# IotaWatt4_4.net
KiCad netlist of a schematic drawn in EAGLE
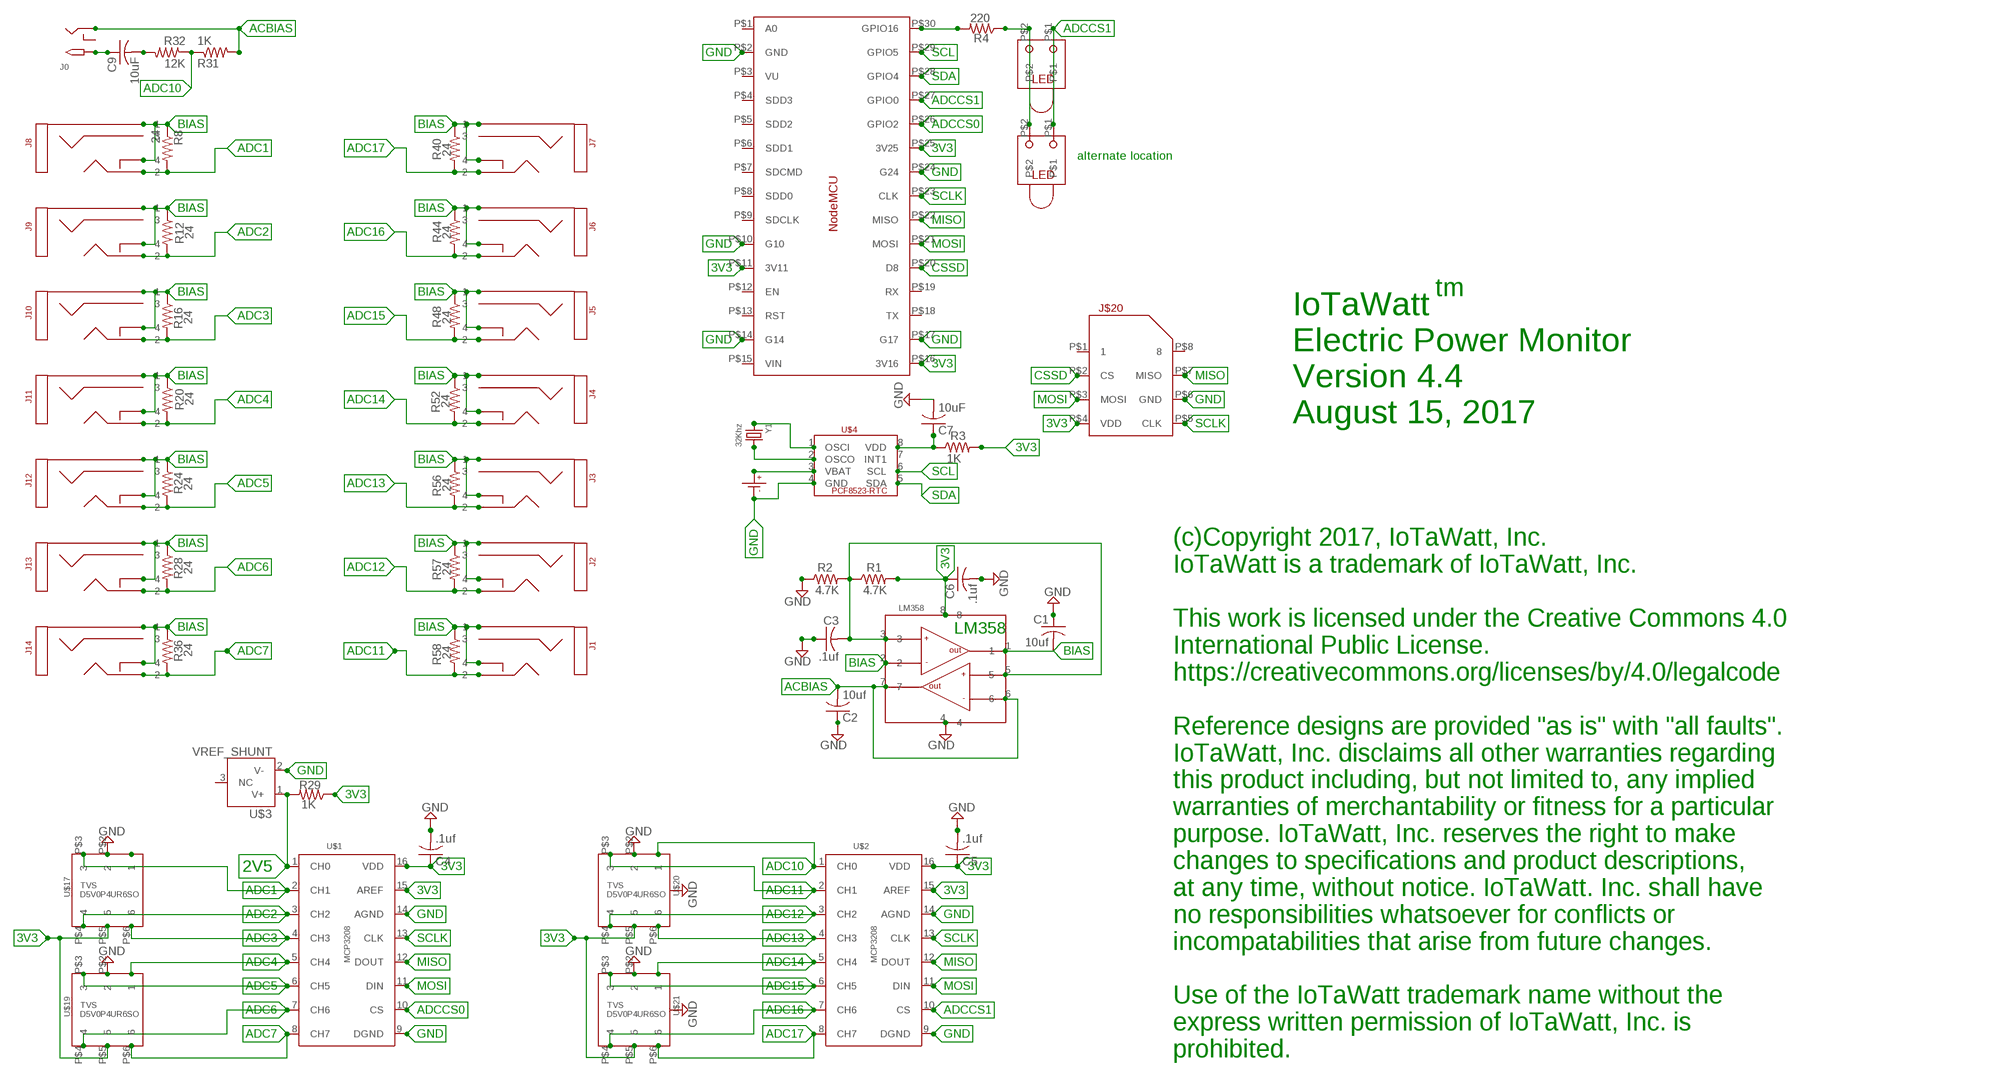
[diagram p0: schematic, sheet 1]

(export (version "E")
  (design (tool "Eeschema 10.0.6"))
  (components
    (comp (ref "C1")
      (value "10uf")
      (footprint "eagle-import:C0805")
      (libsource (lib "eagle-import") (part "C-USC0805"))
    )
    (comp (ref "C2")
      (value "10uf")
      (footprint "eagle-import:C0805")
      (libsource (lib "eagle-import") (part "C-USC0805"))
    )
    (comp (ref "C3")
      (value ".1uf")
      (footprint "eagle-import:C0805")
      (libsource (lib "eagle-import") (part "C-USC0805"))
    )
    (comp (ref "C4")
      (value ".1uf")
      (footprint "eagle-import:C0805")
      (libsource (lib "eagle-import") (part "C-USC0805"))
    )
    (comp (ref "C5")
      (value ".1uf")
      (footprint "eagle-import:C0805")
      (libsource (lib "eagle-import") (part "C-USC0805"))
    )
    (comp (ref "C6")
      (value ".1uf")
      (footprint "eagle-import:C0805")
      (libsource (lib "eagle-import") (part "C-USC0805"))
    )
    (comp (ref "C7")
      (value "10uF")
      (footprint "eagle-import:C0805")
      (libsource (lib "eagle-import") (part "C-USC0805"))
    )
    (comp (ref "C9")
      (value "10uF")
      (footprint "eagle-import:C0805")
      (libsource (lib "eagle-import") (part "C-USC0805"))
    )
    (comp (ref "J$20")
      (value "MICROSD_PUSH/PULL")
      (footprint "eagle-import:MICROSD")
      (libsource (lib "eagle-import") (part "MICROSD_PUSH/PULL"))
    )
    (comp (ref "J0")
      (value "2.1MMJACKSMT")
      (footprint "eagle-import:DCJACK_2MM_SMT")
      (libsource (lib "eagle-import") (part "2.1MMJACKSMT"))
    )
    (comp (ref "J1")
      (value "STEREO_SMD")
      (footprint "eagle-import:STEREO_SMT")
      (libsource (lib "eagle-import") (part "STEREO_SMD"))
    )
    (comp (ref "J2")
      (value "STEREO_SMD")
      (footprint "eagle-import:STEREO_SMT")
      (libsource (lib "eagle-import") (part "STEREO_SMD"))
    )
    (comp (ref "J3")
      (value "STEREO_SMD")
      (footprint "eagle-import:STEREO_SMT")
      (libsource (lib "eagle-import") (part "STEREO_SMD"))
    )
    (comp (ref "J4")
      (value "STEREO_SMD")
      (footprint "eagle-import:STEREO_SMT")
      (libsource (lib "eagle-import") (part "STEREO_SMD"))
    )
    (comp (ref "J5")
      (value "STEREO_SMD")
      (footprint "eagle-import:STEREO_SMT")
      (libsource (lib "eagle-import") (part "STEREO_SMD"))
    )
    (comp (ref "J6")
      (value "STEREO_SMD")
      (footprint "eagle-import:STEREO_SMT")
      (libsource (lib "eagle-import") (part "STEREO_SMD"))
    )
    (comp (ref "J7")
      (value "STEREO_SMD")
      (footprint "eagle-import:STEREO_SMT")
      (libsource (lib "eagle-import") (part "STEREO_SMD"))
    )
    (comp (ref "J8")
      (value "STEREO_SMD")
      (footprint "eagle-import:STEREO_SMT")
      (libsource (lib "eagle-import") (part "STEREO_SMD"))
    )
    (comp (ref "J9")
      (value "STEREO_SMD")
      (footprint "eagle-import:STEREO_SMT")
      (libsource (lib "eagle-import") (part "STEREO_SMD"))
    )
    (comp (ref "J10")
      (value "STEREO_SMD")
      (footprint "eagle-import:STEREO_SMT")
      (libsource (lib "eagle-import") (part "STEREO_SMD"))
    )
    (comp (ref "J11")
      (value "STEREO_SMD")
      (footprint "eagle-import:STEREO_SMT")
      (libsource (lib "eagle-import") (part "STEREO_SMD"))
    )
    (comp (ref "J12")
      (value "STEREO_SMD")
      (footprint "eagle-import:STEREO_SMT")
      (libsource (lib "eagle-import") (part "STEREO_SMD"))
    )
    (comp (ref "J13")
      (value "STEREO_SMD")
      (footprint "eagle-import:STEREO_SMT")
      (libsource (lib "eagle-import") (part "STEREO_SMD"))
    )
    (comp (ref "J14")
      (value "STEREO_SMD")
      (footprint "eagle-import:STEREO_SMT")
      (libsource (lib "eagle-import") (part "STEREO_SMD"))
    )
    (comp (ref "R1")
      (value "4.7K")
      (footprint "eagle-import:R0805")
      (libsource (lib "eagle-import") (part "R-US_R0805"))
    )
    (comp (ref "R2")
      (value "4.7K")
      (footprint "eagle-import:R0805")
      (libsource (lib "eagle-import") (part "R-US_R0805"))
    )
    (comp (ref "R3")
      (value "1K")
      (footprint "eagle-import:R0805")
      (libsource (lib "eagle-import") (part "R-US_R0805"))
    )
    (comp (ref "R4")
      (value "220")
      (footprint "eagle-import:R0805")
      (libsource (lib "eagle-import") (part "R-US_R0805"))
    )
    (comp (ref "R8")
      (value "24")
      (footprint "eagle-import:R0805")
      (libsource (lib "eagle-import") (part "R-US_R0805"))
    )
    (comp (ref "R12")
      (value "24")
      (footprint "eagle-import:R0805")
      (libsource (lib "eagle-import") (part "R-US_R0805"))
    )
    (comp (ref "R16")
      (value "24")
      (footprint "eagle-import:R0805")
      (libsource (lib "eagle-import") (part "R-US_R0805"))
    )
    (comp (ref "R20")
      (value "24")
      (footprint "eagle-import:R0805")
      (libsource (lib "eagle-import") (part "R-US_R0805"))
    )
    (comp (ref "R24")
      (value "24")
      (footprint "eagle-import:R0805")
      (libsource (lib "eagle-import") (part "R-US_R0805"))
    )
    (comp (ref "R28")
      (value "24")
      (footprint "eagle-import:R0805")
      (libsource (lib "eagle-import") (part "R-US_R0805"))
    )
    (comp (ref "R29")
      (value "1K")
      (footprint "eagle-import:R0805")
      (libsource (lib "eagle-import") (part "R-US_R0805"))
    )
    (comp (ref "R31")
      (value "1K")
      (footprint "eagle-import:R0805")
      (libsource (lib "eagle-import") (part "R-US_R0805"))
    )
    (comp (ref "R32")
      (value "12K")
      (footprint "eagle-import:R0805")
      (libsource (lib "eagle-import") (part "R-US_R0805"))
    )
    (comp (ref "R36")
      (value "24")
      (footprint "eagle-import:R0805")
      (libsource (lib "eagle-import") (part "R-US_R0805"))
    )
    (comp (ref "R40")
      (value "24")
      (footprint "eagle-import:R0805")
      (libsource (lib "eagle-import") (part "R-US_R0805"))
    )
    (comp (ref "R44")
      (value "24")
      (footprint "eagle-import:R0805")
      (libsource (lib "eagle-import") (part "R-US_R0805"))
    )
    (comp (ref "R48")
      (value "24")
      (footprint "eagle-import:R0805")
      (libsource (lib "eagle-import") (part "R-US_R0805"))
    )
    (comp (ref "R52")
      (value "24")
      (footprint "eagle-import:R0805")
      (libsource (lib "eagle-import") (part "R-US_R0805"))
    )
    (comp (ref "R56")
      (value "24")
      (footprint "eagle-import:R0805")
      (libsource (lib "eagle-import") (part "R-US_R0805"))
    )
    (comp (ref "R57")
      (value "24")
      (footprint "eagle-import:R0805")
      (libsource (lib "eagle-import") (part "R-US_R0805"))
    )
    (comp (ref "R58")
      (value "24")
      (footprint "eagle-import:R0805")
      (libsource (lib "eagle-import") (part "R-US_R0805"))
    )
    (comp (ref "U$1")
      (value "MCP3208")
      (footprint "eagle-import:SOIC_16")
      (libsource (lib "eagle-import") (part "MCP3208"))
    )
    (comp (ref "U$2")
      (value "MCP3208")
      (footprint "eagle-import:SOIC_16")
      (libsource (lib "eagle-import") (part "MCP3208"))
    )
    (comp (ref "U$3")
      (value "VREF_SHUNT")
      (footprint "eagle-import:SOT23_3")
      (libsource (lib "eagle-import") (part "VREF_SHUNT"))
    )
    (comp (ref "U$4")
      (value "PCF8523_RTC")
      (footprint "eagle-import:SOIC_8")
      (libsource (lib "eagle-import") (part "PCF8523_RTC"))
    )
    (comp (ref "U$15")
      (value "LED_RT_TRH")
      (footprint "eagle-import:LED_TH_RT")
      (libsource (lib "eagle-import") (part "LED_RT_TRH"))
    )
    (comp (ref "U$16")
      (value "NODEMCU")
      (footprint "eagle-import:NODEMCU")
      (libsource (lib "eagle-import") (part "NODEMCU"))
    )
    (comp (ref "U$17")
      (value "TVS_4CHAN_ARRAYSC-74")
      (footprint "eagle-import:SC-74")
      (libsource (lib "eagle-import") (part "TVS_4CHAN_ARRAYSC-74"))
    )
    (comp (ref "U$18")
      (value "CR1220SMD")
      (footprint "eagle-import:CR1220SMD")
      (libsource (lib "eagle-import") (part "CR1220SMD"))
    )
    (comp (ref "U$19")
      (value "TVS_4CHAN_ARRAYSC-74")
      (footprint "eagle-import:SC-74")
      (libsource (lib "eagle-import") (part "TVS_4CHAN_ARRAYSC-74"))
    )
    (comp (ref "U$20")
      (value "TVS_4CHAN_ARRAYSC-74")
      (footprint "eagle-import:SC-74")
      (libsource (lib "eagle-import") (part "TVS_4CHAN_ARRAYSC-74"))
    )
    (comp (ref "U$21")
      (value "TVS_4CHAN_ARRAYSC-74")
      (footprint "eagle-import:SC-74")
      (libsource (lib "eagle-import") (part "TVS_4CHAN_ARRAYSC-74"))
    )
    (comp (ref "U$22")
      (value "LM358_DUAL_OP-AMP")
      (footprint "eagle-import:SOIC_8")
      (libsource (lib "eagle-import") (part "LM358_DUAL_OP-AMP"))
    )
    (comp (ref "U$23")
      (value "LED_RT_TRH")
      (footprint "eagle-import:LED_TH_RT")
      (libsource (lib "eagle-import") (part "LED_RT_TRH"))
    )
    (comp (ref "Y1")
      (value "32Khz")
      (footprint "eagle-import:CRYSTAL_8X3.8")
      (libsource (lib "eagle-import") (part "CRYSTAL8X3.8SMT"))
    )
  )
  (nets
    (net (code "1") (name "2V5") (class "Default")
      (node (ref "R29") (pin "2") (pinfunction "2_2") (pintype "passive"))
      (node (ref "U$1") (pin "1") (pinfunction "CH0_1") (pintype "input"))
      (node (ref "U$3") (pin "1") (pinfunction "V+_1") (pintype "bidirectional"))
    )
    (net (code "2") (name "3V3") (class "Default")
      (node (ref "C4") (pin "1") (pinfunction "1_1") (pintype "passive"))
      (node (ref "C5") (pin "1") (pinfunction "1_1") (pintype "passive"))
      (node (ref "C6") (pin "1") (pinfunction "1_1") (pintype "passive"))
      (node (ref "J$20") (pin "P$4") (pinfunction "VDD_P$4") (pintype "bidirectional"))
      (node (ref "R1") (pin "2") (pinfunction "2_2") (pintype "passive"))
      (node (ref "R29") (pin "1") (pinfunction "1_1") (pintype "passive"))
      (node (ref "R3") (pin "2") (pinfunction "2_2") (pintype "passive"))
      (node (ref "U$1") (pin "15") (pinfunction "AREF_15") (pintype "input"))
      (node (ref "U$1") (pin "16") (pinfunction "VDD_16") (pintype "bidirectional"))
      (node (ref "U$16") (pin "P$11") (pinfunction "3V11_P$11") (pintype "bidirectional"))
      (node (ref "U$16") (pin "P$16") (pinfunction "3V16_P$16") (pintype "bidirectional"))
      (node (ref "U$16") (pin "P$25") (pinfunction "3V25_P$25") (pintype "bidirectional"))
      (node (ref "U$17") (pin "P$5") (pinfunction "5_P$5") (pintype "bidirectional"))
      (node (ref "U$19") (pin "P$5") (pinfunction "5_P$5") (pintype "bidirectional"))
      (node (ref "U$2") (pin "15") (pinfunction "AREF_15") (pintype "input"))
      (node (ref "U$2") (pin "16") (pinfunction "VDD_16") (pintype "bidirectional"))
      (node (ref "U$20") (pin "P$5") (pinfunction "5_P$5") (pintype "bidirectional"))
      (node (ref "U$21") (pin "P$5") (pinfunction "5_P$5") (pintype "bidirectional"))
      (node (ref "U$22") (pin "8") (pinfunction "8_8") (pintype "bidirectional"))
    )
    (net (code "3") (name "ACBIAS") (class "Default")
      (node (ref "C2") (pin "2") (pinfunction "2_2") (pintype "passive"))
      (node (ref "J0") (pin "GND") (pinfunction "RING_GND") (pintype "bidirectional"))
      (node (ref "R31") (pin "2") (pinfunction "2_2") (pintype "passive"))
      (node (ref "U$22") (pin "6") (pinfunction "6_6") (pintype "bidirectional"))
      (node (ref "U$22") (pin "7") (pinfunction "7_7") (pintype "bidirectional"))
    )
    (net (code "4") (name "ADC1") (class "Default")
      (node (ref "J8") (pin "P$2") (pinfunction "2_P$2") (pintype "bidirectional"))
      (node (ref "R8") (pin "2") (pinfunction "2_2") (pintype "passive"))
      (node (ref "U$1") (pin "2") (pinfunction "CH1_2") (pintype "input"))
      (node (ref "U$17") (pin "P$3") (pinfunction "3_P$3") (pintype "bidirectional"))
    )
    (net (code "5") (name "ADC2") (class "Default")
      (node (ref "J9") (pin "P$2") (pinfunction "2_P$2") (pintype "bidirectional"))
      (node (ref "R12") (pin "2") (pinfunction "2_2") (pintype "passive"))
      (node (ref "U$1") (pin "3") (pinfunction "CH2_3") (pintype "input"))
      (node (ref "U$17") (pin "P$4") (pinfunction "4_P$4") (pintype "bidirectional"))
    )
    (net (code "6") (name "ADC3") (class "Default")
      (node (ref "J10") (pin "P$2") (pinfunction "2_P$2") (pintype "bidirectional"))
      (node (ref "R16") (pin "2") (pinfunction "2_2") (pintype "passive"))
      (node (ref "U$1") (pin "4") (pinfunction "CH3_4") (pintype "input"))
      (node (ref "U$17") (pin "P$6") (pinfunction "6_P$6") (pintype "bidirectional"))
    )
    (net (code "7") (name "ADC4") (class "Default")
      (node (ref "J11") (pin "P$2") (pinfunction "2_P$2") (pintype "bidirectional"))
      (node (ref "R20") (pin "2") (pinfunction "2_2") (pintype "passive"))
      (node (ref "U$1") (pin "5") (pinfunction "CH4_5") (pintype "bidirectional"))
      (node (ref "U$19") (pin "P$1") (pinfunction "1_P$1") (pintype "bidirectional"))
    )
    (net (code "8") (name "ADC5") (class "Default")
      (node (ref "J12") (pin "P$2") (pinfunction "2_P$2") (pintype "bidirectional"))
      (node (ref "R24") (pin "2") (pinfunction "2_2") (pintype "passive"))
      (node (ref "U$1") (pin "6") (pinfunction "CH5_6") (pintype "bidirectional"))
      (node (ref "U$19") (pin "P$3") (pinfunction "3_P$3") (pintype "bidirectional"))
    )
    (net (code "9") (name "ADC6") (class "Default")
      (node (ref "J13") (pin "P$2") (pinfunction "2_P$2") (pintype "bidirectional"))
      (node (ref "R28") (pin "2") (pinfunction "2_2") (pintype "passive"))
      (node (ref "U$1") (pin "7") (pinfunction "CH6_7") (pintype "input"))
      (node (ref "U$19") (pin "P$4") (pinfunction "4_P$4") (pintype "bidirectional"))
    )
    (net (code "10") (name "ADC7") (class "Default")
      (node (ref "J14") (pin "P$2") (pinfunction "2_P$2") (pintype "bidirectional"))
      (node (ref "R36") (pin "2") (pinfunction "2_2") (pintype "passive"))
      (node (ref "U$1") (pin "8") (pinfunction "CH7_8") (pintype "bidirectional"))
      (node (ref "U$19") (pin "P$6") (pinfunction "6_P$6") (pintype "bidirectional"))
    )
    (net (code "11") (name "ADC10") (class "Default")
      (node (ref "R31") (pin "1") (pinfunction "1_1") (pintype "passive"))
      (node (ref "R32") (pin "1") (pinfunction "1_1") (pintype "passive"))
      (node (ref "U$2") (pin "1") (pinfunction "CH0_1") (pintype "input"))
      (node (ref "U$20") (pin "P$1") (pinfunction "1_P$1") (pintype "bidirectional"))
    )
    (net (code "12") (name "ADC11") (class "Default")
      (node (ref "J1") (pin "P$2") (pinfunction "2_P$2") (pintype "bidirectional"))
      (node (ref "R58") (pin "2") (pinfunction "2_2") (pintype "passive"))
      (node (ref "U$2") (pin "2") (pinfunction "CH1_2") (pintype "input"))
      (node (ref "U$20") (pin "P$3") (pinfunction "3_P$3") (pintype "bidirectional"))
    )
    (net (code "13") (name "ADC12") (class "Default")
      (node (ref "J2") (pin "P$2") (pinfunction "2_P$2") (pintype "bidirectional"))
      (node (ref "R57") (pin "2") (pinfunction "2_2") (pintype "passive"))
      (node (ref "U$2") (pin "3") (pinfunction "CH2_3") (pintype "input"))
      (node (ref "U$20") (pin "P$4") (pinfunction "4_P$4") (pintype "bidirectional"))
    )
    (net (code "14") (name "ADC13") (class "Default")
      (node (ref "J3") (pin "P$2") (pinfunction "2_P$2") (pintype "bidirectional"))
      (node (ref "R56") (pin "2") (pinfunction "2_2") (pintype "passive"))
      (node (ref "U$2") (pin "4") (pinfunction "CH3_4") (pintype "input"))
      (node (ref "U$20") (pin "P$6") (pinfunction "6_P$6") (pintype "bidirectional"))
    )
    (net (code "15") (name "ADC14") (class "Default")
      (node (ref "J4") (pin "P$2") (pinfunction "2_P$2") (pintype "bidirectional"))
      (node (ref "R52") (pin "2") (pinfunction "2_2") (pintype "passive"))
      (node (ref "U$2") (pin "5") (pinfunction "CH4_5") (pintype "bidirectional"))
      (node (ref "U$21") (pin "P$1") (pinfunction "1_P$1") (pintype "bidirectional"))
    )
    (net (code "16") (name "ADC15") (class "Default")
      (node (ref "J5") (pin "P$2") (pinfunction "2_P$2") (pintype "bidirectional"))
      (node (ref "R48") (pin "2") (pinfunction "2_2") (pintype "passive"))
      (node (ref "U$2") (pin "6") (pinfunction "CH5_6") (pintype "bidirectional"))
      (node (ref "U$21") (pin "P$3") (pinfunction "3_P$3") (pintype "bidirectional"))
    )
    (net (code "17") (name "ADC16") (class "Default")
      (node (ref "J6") (pin "P$2") (pinfunction "2_P$2") (pintype "bidirectional"))
      (node (ref "R44") (pin "2") (pinfunction "2_2") (pintype "passive"))
      (node (ref "U$2") (pin "7") (pinfunction "CH6_7") (pintype "input"))
      (node (ref "U$21") (pin "P$4") (pinfunction "4_P$4") (pintype "bidirectional"))
    )
    (net (code "18") (name "ADC17") (class "Default")
      (node (ref "J7") (pin "P$2") (pinfunction "2_P$2") (pintype "bidirectional"))
      (node (ref "R40") (pin "2") (pinfunction "2_2") (pintype "passive"))
      (node (ref "U$2") (pin "8") (pinfunction "CH7_8") (pintype "bidirectional"))
      (node (ref "U$21") (pin "P$6") (pinfunction "6_P$6") (pintype "bidirectional"))
    )
    (net (code "19") (name "ADCCS0") (class "Default")
      (node (ref "U$1") (pin "10") (pinfunction "CS_10") (pintype "input"))
      (node (ref "U$16") (pin "P$26") (pinfunction "GPIO2_P$26") (pintype "bidirectional"))
    )
    (net (code "20") (name "ADCCS1") (class "Default")
      (node (ref "U$15") (pin "P$1") (pinfunction "P$1_P$1") (pintype "bidirectional"))
      (node (ref "U$16") (pin "P$27") (pinfunction "GPIO0_P$27") (pintype "bidirectional"))
      (node (ref "U$2") (pin "10") (pinfunction "CS_10") (pintype "input"))
      (node (ref "U$23") (pin "P$1") (pinfunction "P$1_P$1") (pintype "bidirectional"))
    )
    (net (code "21") (name "BIAS") (class "Default")
      (node (ref "C1") (pin "2") (pinfunction "2_2") (pintype "passive"))
      (node (ref "J1") (pin "P$1") (pinfunction "1_P$1") (pintype "bidirectional"))
      (node (ref "J1") (pin "P$4") (pinfunction "4_P$4") (pintype "bidirectional"))
      (node (ref "J10") (pin "P$1") (pinfunction "1_P$1") (pintype "bidirectional"))
      (node (ref "J10") (pin "P$4") (pinfunction "4_P$4") (pintype "bidirectional"))
      (node (ref "J11") (pin "P$1") (pinfunction "1_P$1") (pintype "bidirectional"))
      (node (ref "J11") (pin "P$4") (pinfunction "4_P$4") (pintype "bidirectional"))
      (node (ref "J12") (pin "P$1") (pinfunction "1_P$1") (pintype "bidirectional"))
      (node (ref "J12") (pin "P$4") (pinfunction "4_P$4") (pintype "bidirectional"))
      (node (ref "J13") (pin "P$1") (pinfunction "1_P$1") (pintype "bidirectional"))
      (node (ref "J13") (pin "P$4") (pinfunction "4_P$4") (pintype "bidirectional"))
      (node (ref "J14") (pin "P$1") (pinfunction "1_P$1") (pintype "bidirectional"))
      (node (ref "J14") (pin "P$4") (pinfunction "4_P$4") (pintype "bidirectional"))
      (node (ref "J2") (pin "P$1") (pinfunction "1_P$1") (pintype "bidirectional"))
      (node (ref "J2") (pin "P$4") (pinfunction "4_P$4") (pintype "bidirectional"))
      (node (ref "J3") (pin "P$1") (pinfunction "1_P$1") (pintype "bidirectional"))
      (node (ref "J3") (pin "P$4") (pinfunction "4_P$4") (pintype "bidirectional"))
      (node (ref "J4") (pin "P$1") (pinfunction "1_P$1") (pintype "bidirectional"))
      (node (ref "J4") (pin "P$4") (pinfunction "4_P$4") (pintype "bidirectional"))
      (node (ref "J5") (pin "P$1") (pinfunction "1_P$1") (pintype "bidirectional"))
      (node (ref "J5") (pin "P$4") (pinfunction "4_P$4") (pintype "bidirectional"))
      (node (ref "J6") (pin "P$1") (pinfunction "1_P$1") (pintype "bidirectional"))
      (node (ref "J6") (pin "P$4") (pinfunction "4_P$4") (pintype "bidirectional"))
      (node (ref "J7") (pin "P$1") (pinfunction "1_P$1") (pintype "bidirectional"))
      (node (ref "J7") (pin "P$4") (pinfunction "4_P$4") (pintype "bidirectional"))
      (node (ref "J8") (pin "P$1") (pinfunction "1_P$1") (pintype "bidirectional"))
      (node (ref "J8") (pin "P$4") (pinfunction "4_P$4") (pintype "bidirectional"))
      (node (ref "J9") (pin "P$1") (pinfunction "1_P$1") (pintype "bidirectional"))
      (node (ref "J9") (pin "P$4") (pinfunction "4_P$4") (pintype "bidirectional"))
      (node (ref "R12") (pin "1") (pinfunction "1_1") (pintype "passive"))
      (node (ref "R16") (pin "1") (pinfunction "1_1") (pintype "passive"))
      (node (ref "R20") (pin "1") (pinfunction "1_1") (pintype "passive"))
      (node (ref "R24") (pin "1") (pinfunction "1_1") (pintype "passive"))
      (node (ref "R28") (pin "1") (pinfunction "1_1") (pintype "passive"))
      (node (ref "R36") (pin "1") (pinfunction "1_1") (pintype "passive"))
      (node (ref "R40") (pin "1") (pinfunction "1_1") (pintype "passive"))
      (node (ref "R44") (pin "1") (pinfunction "1_1") (pintype "passive"))
      (node (ref "R48") (pin "1") (pinfunction "1_1") (pintype "passive"))
      (node (ref "R52") (pin "1") (pinfunction "1_1") (pintype "passive"))
      (node (ref "R56") (pin "1") (pinfunction "1_1") (pintype "passive"))
      (node (ref "R57") (pin "1") (pinfunction "1_1") (pintype "passive"))
      (node (ref "R58") (pin "1") (pinfunction "1_1") (pintype "passive"))
      (node (ref "R8") (pin "1") (pinfunction "1_1") (pintype "passive"))
      (node (ref "U$22") (pin "1") (pinfunction "1_1") (pintype "bidirectional"))
      (node (ref "U$22") (pin "2") (pinfunction "2_2") (pintype "bidirectional"))
    )
    (net (code "22") (name "CSSD") (class "Default")
      (node (ref "J$20") (pin "P$2") (pinfunction "CS_P$2") (pintype "bidirectional"))
      (node (ref "U$16") (pin "P$20") (pinfunction "D8_P$20") (pintype "bidirectional"))
    )
    (net (code "23") (name "GND") (class "Default")
      (node (ref "C1") (pin "1") (pinfunction "1_1") (pintype "passive"))
      (node (ref "C2") (pin "1") (pinfunction "1_1") (pintype "passive"))
      (node (ref "C3") (pin "1") (pinfunction "1_1") (pintype "passive"))
      (node (ref "C4") (pin "2") (pinfunction "2_2") (pintype "passive"))
      (node (ref "C5") (pin "2") (pinfunction "2_2") (pintype "passive"))
      (node (ref "C6") (pin "2") (pinfunction "2_2") (pintype "passive"))
      (node (ref "C7") (pin "2") (pinfunction "2_2") (pintype "passive"))
      (node (ref "J$20") (pin "P$6") (pinfunction "GND_P$6") (pintype "bidirectional"))
      (node (ref "R2") (pin "1") (pinfunction "1_1") (pintype "passive"))
      (node (ref "U$1") (pin "14") (pinfunction "AGND_14") (pintype "input"))
      (node (ref "U$1") (pin "9") (pinfunction "DGND_9") (pintype "bidirectional"))
      (node (ref "U$16") (pin "P$10") (pinfunction "G10_P$10") (pintype "bidirectional"))
      (node (ref "U$16") (pin "P$14") (pinfunction "G14_P$14") (pintype "bidirectional"))
      (node (ref "U$16") (pin "P$17") (pinfunction "G17_P$17") (pintype "bidirectional"))
      (node (ref "U$16") (pin "P$2") (pinfunction "GND_P$2") (pintype "bidirectional"))
      (node (ref "U$16") (pin "P$24") (pinfunction "G24_P$24") (pintype "bidirectional"))
      (node (ref "U$17") (pin "P$2") (pinfunction "2_P$2") (pintype "bidirectional"))
      (node (ref "U$18") (pin "P-") (pinfunction "P$-_P-") (pintype "bidirectional"))
      (node (ref "U$19") (pin "P$2") (pinfunction "2_P$2") (pintype "bidirectional"))
      (node (ref "U$2") (pin "14") (pinfunction "AGND_14") (pintype "input"))
      (node (ref "U$2") (pin "9") (pinfunction "DGND_9") (pintype "bidirectional"))
      (node (ref "U$20") (pin "P$2") (pinfunction "2_P$2") (pintype "bidirectional"))
      (node (ref "U$21") (pin "P$2") (pinfunction "2_P$2") (pintype "bidirectional"))
      (node (ref "U$22") (pin "4") (pinfunction "4_4") (pintype "bidirectional"))
      (node (ref "U$3") (pin "2") (pinfunction "V-_2") (pintype "bidirectional"))
      (node (ref "U$4") (pin "4") (pinfunction "GND_4") (pintype "bidirectional"))
    )
    (net (code "24") (name "MISO") (class "Default")
      (node (ref "J$20") (pin "P$7") (pinfunction "MISO_P$7") (pintype "bidirectional"))
      (node (ref "U$1") (pin "12") (pinfunction "DOUT_12") (pintype "bidirectional"))
      (node (ref "U$16") (pin "P$22") (pinfunction "MISO_P$22") (pintype "bidirectional"))
      (node (ref "U$2") (pin "12") (pinfunction "DOUT_12") (pintype "bidirectional"))
    )
    (net (code "25") (name "MOSI") (class "Default")
      (node (ref "J$20") (pin "P$3") (pinfunction "MOSI_P$3") (pintype "bidirectional"))
      (node (ref "U$1") (pin "11") (pinfunction "DIN_11") (pintype "input"))
      (node (ref "U$16") (pin "P$21") (pinfunction "MOSI_P$21") (pintype "bidirectional"))
      (node (ref "U$2") (pin "11") (pinfunction "DIN_11") (pintype "input"))
    )
    (net (code "26") (name "Net-(C3-Pad2)") (class "Default")
      (node (ref "C3") (pin "2") (pinfunction "2_2") (pintype "passive"))
      (node (ref "R1") (pin "1") (pinfunction "1_1") (pintype "passive"))
      (node (ref "R2") (pin "2") (pinfunction "2_2") (pintype "passive"))
      (node (ref "U$22") (pin "3") (pinfunction "3_3") (pintype "bidirectional"))
      (node (ref "U$22") (pin "5") (pinfunction "5_5") (pintype "bidirectional"))
    )
    (net (code "27") (name "Net-(C9-Pad2)") (class "Default")
      (node (ref "C9") (pin "2") (pinfunction "2_2") (pintype "passive"))
      (node (ref "R32") (pin "2") (pinfunction "2_2") (pintype "passive"))
    )
    (net (code "28") (name "Net-(J0-TIP)") (class "Default")
      (node (ref "C9") (pin "1") (pinfunction "1_1") (pintype "passive"))
      (node (ref "J0") (pin "PWR2") (pinfunction "TIP_PWR2") (pintype "bidirectional"))
    )
    (net (code "29") (name "Net-(R4-Pad1)") (class "Default")
      (node (ref "R4") (pin "1") (pinfunction "1_1") (pintype "passive"))
      (node (ref "U$15") (pin "P$2") (pinfunction "P$2_P$2") (pintype "bidirectional"))
      (node (ref "U$23") (pin "P$2") (pinfunction "P$2_P$2") (pintype "bidirectional"))
    )
    (net (code "30") (name "Net-(U$4-OSCI)") (class "Default")
      (node (ref "U$4") (pin "1") (pinfunction "OSCI_1") (pintype "bidirectional"))
      (node (ref "Y1") (pin "P$1") (pinfunction "1_P$1") (pintype "passive"))
    )
    (net (code "31") (name "Net-(U$4-OSCO)") (class "Default")
      (node (ref "U$4") (pin "2") (pinfunction "OSCO_2") (pintype "bidirectional"))
      (node (ref "Y1") (pin "P$4") (pinfunction "2_P$4") (pintype "passive"))
    )
    (net (code "32") (name "Net-(U$4-VDD)") (class "Default")
      (node (ref "C7") (pin "1") (pinfunction "1_1") (pintype "passive"))
      (node (ref "R3") (pin "1") (pinfunction "1_1") (pintype "passive"))
      (node (ref "U$4") (pin "8") (pinfunction "VDD_8") (pintype "bidirectional"))
    )
    (net (code "33") (name "Net-(U$16-GPIO16)") (class "Default")
      (node (ref "R4") (pin "2") (pinfunction "2_2") (pintype "passive"))
      (node (ref "U$16") (pin "P$30") (pinfunction "GPIO16_P$30") (pintype "bidirectional"))
    )
    (net (code "34") (name "Net-(U$18-P$+)") (class "Default")
      (node (ref "U$18") (pin "P+") (pinfunction "P$+_P+") (pintype "bidirectional"))
      (node (ref "U$4") (pin "3") (pinfunction "VBAT_3") (pintype "bidirectional"))
    )
    (net (code "35") (name "SCL") (class "Default")
      (node (ref "U$16") (pin "P$29") (pinfunction "GPIO5_P$29") (pintype "bidirectional"))
      (node (ref "U$4") (pin "6") (pinfunction "SCL_6") (pintype "bidirectional"))
    )
    (net (code "36") (name "SCLK") (class "Default")
      (node (ref "J$20") (pin "P$5") (pinfunction "CLK_P$5") (pintype "bidirectional"))
      (node (ref "U$1") (pin "13") (pinfunction "CLK_13") (pintype "input"))
      (node (ref "U$16") (pin "P$23") (pinfunction "CLK_P$23") (pintype "bidirectional"))
      (node (ref "U$2") (pin "13") (pinfunction "CLK_13") (pintype "input"))
    )
    (net (code "37") (name "SDA") (class "Default")
      (node (ref "U$16") (pin "P$28") (pinfunction "GPIO4_P$28") (pintype "bidirectional"))
      (node (ref "U$4") (pin "5") (pinfunction "SDA_5") (pintype "bidirectional"))
    )
    (net (code "38") (name "unconnected-(J$20-1-PadP$1)") (class "Default")
      (node (ref "J$20") (pin "P$1") (pinfunction "1_P$1") (pintype "bidirectional"))
    )
    (net (code "39") (name "unconnected-(J$20-8-PadP$8)") (class "Default")
      (node (ref "J$20") (pin "P$8") (pinfunction "8_P$8") (pintype "bidirectional"))
    )
    (net (code "40") (name "unconnected-(J0-RING_SW-PadGNDBREAK)") (class "Default")
      (node (ref "J0") (pin "GNDBREAK") (pinfunction "RING_SW_GNDBREAK") (pintype "bidirectional"))
    )
    (net (code "41") (name "unconnected-(J1-3-PadP$3)") (class "Default")
      (node (ref "J1") (pin "P$3") (pinfunction "3_P$3") (pintype "bidirectional"))
    )
    (net (code "42") (name "unconnected-(J2-3-PadP$3)") (class "Default")
      (node (ref "J2") (pin "P$3") (pinfunction "3_P$3") (pintype "bidirectional"))
    )
    (net (code "43") (name "unconnected-(J3-3-PadP$3)") (class "Default")
      (node (ref "J3") (pin "P$3") (pinfunction "3_P$3") (pintype "bidirectional"))
    )
    (net (code "44") (name "unconnected-(J4-3-PadP$3)") (class "Default")
      (node (ref "J4") (pin "P$3") (pinfunction "3_P$3") (pintype "bidirectional"))
    )
    (net (code "45") (name "unconnected-(J5-3-PadP$3)") (class "Default")
      (node (ref "J5") (pin "P$3") (pinfunction "3_P$3") (pintype "bidirectional"))
    )
    (net (code "46") (name "unconnected-(J6-3-PadP$3)") (class "Default")
      (node (ref "J6") (pin "P$3") (pinfunction "3_P$3") (pintype "bidirectional"))
    )
    (net (code "47") (name "unconnected-(J7-3-PadP$3)") (class "Default")
      (node (ref "J7") (pin "P$3") (pinfunction "3_P$3") (pintype "bidirectional"))
    )
    (net (code "48") (name "unconnected-(J8-3-PadP$3)") (class "Default")
      (node (ref "J8") (pin "P$3") (pinfunction "3_P$3") (pintype "bidirectional"))
    )
    (net (code "49") (name "unconnected-(J9-3-PadP$3)") (class "Default")
      (node (ref "J9") (pin "P$3") (pinfunction "3_P$3") (pintype "bidirectional"))
    )
    (net (code "50") (name "unconnected-(J10-3-PadP$3)") (class "Default")
      (node (ref "J10") (pin "P$3") (pinfunction "3_P$3") (pintype "bidirectional"))
    )
    (net (code "51") (name "unconnected-(J11-3-PadP$3)") (class "Default")
      (node (ref "J11") (pin "P$3") (pinfunction "3_P$3") (pintype "bidirectional"))
    )
    (net (code "52") (name "unconnected-(J12-3-PadP$3)") (class "Default")
      (node (ref "J12") (pin "P$3") (pinfunction "3_P$3") (pintype "bidirectional"))
    )
    (net (code "53") (name "unconnected-(J13-3-PadP$3)") (class "Default")
      (node (ref "J13") (pin "P$3") (pinfunction "3_P$3") (pintype "bidirectional"))
    )
    (net (code "54") (name "unconnected-(J14-3-PadP$3)") (class "Default")
      (node (ref "J14") (pin "P$3") (pinfunction "3_P$3") (pintype "bidirectional"))
    )
    (net (code "55") (name "unconnected-(U$3-NC-Pad3)") (class "Default")
      (node (ref "U$3") (pin "3") (pinfunction "NC_3") (pintype "bidirectional"))
    )
    (net (code "56") (name "unconnected-(U$4-INT1-Pad7)") (class "Default")
      (node (ref "U$4") (pin "7") (pinfunction "INT1_7") (pintype "bidirectional"))
    )
    (net (code "57") (name "unconnected-(U$16-A0-PadP$1)") (class "Default")
      (node (ref "U$16") (pin "P$1") (pinfunction "A0_P$1") (pintype "bidirectional"))
    )
    (net (code "58") (name "unconnected-(U$16-EN-PadP$12)") (class "Default")
      (node (ref "U$16") (pin "P$12") (pinfunction "EN_P$12") (pintype "bidirectional"))
    )
    (net (code "59") (name "unconnected-(U$16-RST-PadP$13)") (class "Default")
      (node (ref "U$16") (pin "P$13") (pinfunction "RST_P$13") (pintype "bidirectional"))
    )
    (net (code "60") (name "unconnected-(U$16-RX-PadP$19)") (class "Default")
      (node (ref "U$16") (pin "P$19") (pinfunction "RX_P$19") (pintype "bidirectional"))
    )
    (net (code "61") (name "unconnected-(U$16-SDCLK-PadP$9)") (class "Default")
      (node (ref "U$16") (pin "P$9") (pinfunction "SDCLK_P$9") (pintype "bidirectional"))
    )
    (net (code "62") (name "unconnected-(U$16-SDCMD-PadP$7)") (class "Default")
      (node (ref "U$16") (pin "P$7") (pinfunction "SDCMD_P$7") (pintype "bidirectional"))
    )
    (net (code "63") (name "unconnected-(U$16-SDD0-PadP$8)") (class "Default")
      (node (ref "U$16") (pin "P$8") (pinfunction "SDD0_P$8") (pintype "bidirectional"))
    )
    (net (code "64") (name "unconnected-(U$16-SDD1-PadP$6)") (class "Default")
      (node (ref "U$16") (pin "P$6") (pinfunction "SDD1_P$6") (pintype "bidirectional"))
    )
    (net (code "65") (name "unconnected-(U$16-SDD2-PadP$5)") (class "Default")
      (node (ref "U$16") (pin "P$5") (pinfunction "SDD2_P$5") (pintype "bidirectional"))
    )
    (net (code "66") (name "unconnected-(U$16-SDD3-PadP$4)") (class "Default")
      (node (ref "U$16") (pin "P$4") (pinfunction "SDD3_P$4") (pintype "bidirectional"))
    )
    (net (code "67") (name "unconnected-(U$16-TX-PadP$18)") (class "Default")
      (node (ref "U$16") (pin "P$18") (pinfunction "TX_P$18") (pintype "bidirectional"))
    )
    (net (code "68") (name "unconnected-(U$16-VIN-PadP$15)") (class "Default")
      (node (ref "U$16") (pin "P$15") (pinfunction "VIN_P$15") (pintype "bidirectional"))
    )
    (net (code "69") (name "unconnected-(U$16-VU-PadP$3)") (class "Default")
      (node (ref "U$16") (pin "P$3") (pinfunction "VU_P$3") (pintype "bidirectional"))
    )
    (net (code "70") (name "unconnected-(U$17-1-PadP$1)") (class "Default")
      (node (ref "U$17") (pin "P$1") (pinfunction "1_P$1") (pintype "bidirectional"))
    )
  )
)
